# Pressure_sensor.net
KiCad netlist of a schematic drawn in Altium Designer
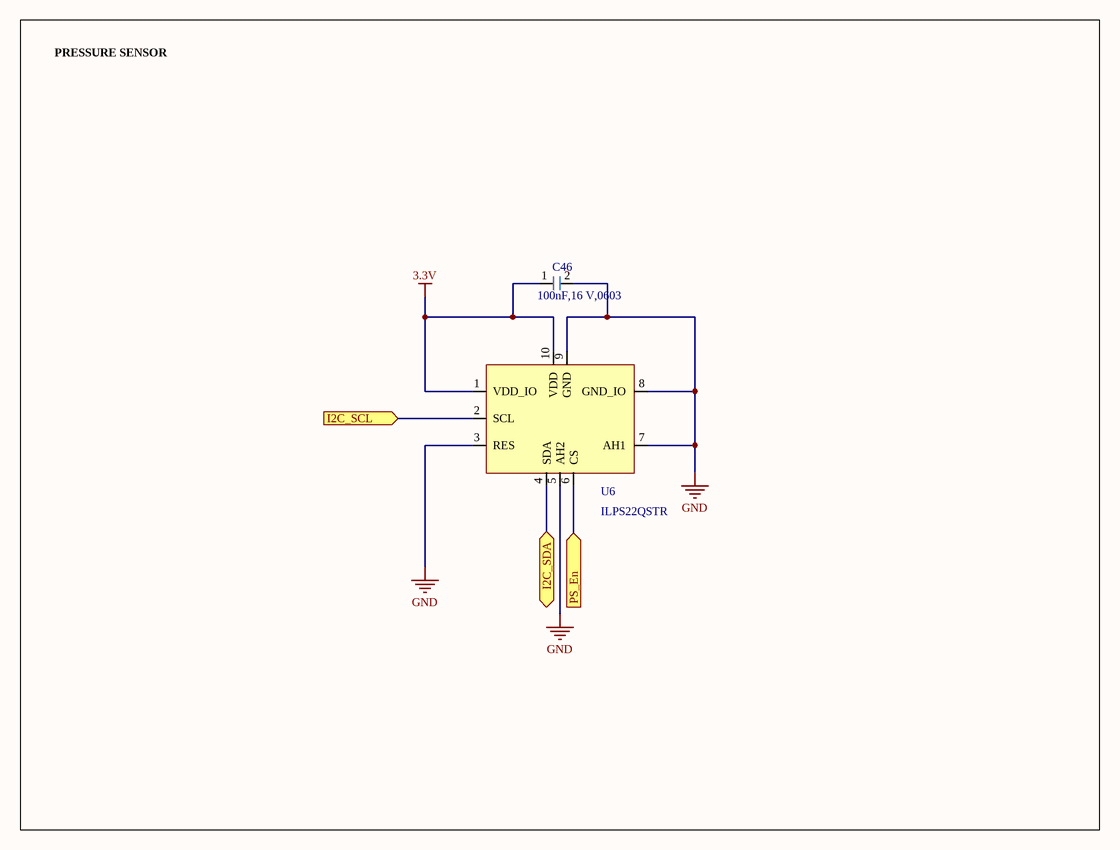
[diagram p0: Pressure sensor.SchDoc]

(export (version "E")
  (design (tool "Eeschema 10.0.6"))
  (components
    (comp (ref "C46")
      (value "CC0603KRX7R7BB104")
      (footprint "BMS_V2.1_Adv:CAPC1608X05N 0603")
      (description "Multilayer Ceramic Capacitor, 100 nF, 16V, ±10%,  X7R 0603 [1608 Metric]")
      (fields
        (field (name "MANUFACTURER") "Yageo")
        (field (name "TOLERANCE") "10%")
        (field (name "VALUE DISPLAY") "100nF,16 V,0603")
      )
      (libsource (lib "BMS_V2.1_Adv") (part "Cap_CC0603KRX7R7BB104"))
    )
    (comp (ref "U6")
      (value "ILPS22QSTR")
      (footprint "BMS_V2.1_Adv:QFN50P200X200X80-10N")
      (description "Pressure Sensor 3.77PSI ~ 58.89PSI (26kPa ~ 406kPa) Absolute 24 b 10-WFLGA")
      (fields (field (name "MANUFACTURER") "ST") (field (name "VOLTAGE") "3.3V"))
      (libsource (lib "BMS_V2.1_Adv") (part "IC_ILPS22QSTR"))
    )
  )
  (nets
    (net (code "1") (name "/I2C_SCL") (class "Default")
      (node (ref "U6") (pin "2") (pinfunction "SCL_2") (pintype "passive"))
    )
    (net (code "2") (name "/I2C_SDA") (class "Default")
      (node (ref "U6") (pin "4") (pinfunction "SDA_4") (pintype "passive"))
    )
    (net (code "3") (name "/PS_En") (class "Default")
      (node (ref "U6") (pin "6") (pinfunction "CS_6") (pintype "passive"))
    )
    (net (code "4") (name "3.3V") (class "Default")
      (node (ref "C46") (pin "1") (pinfunction "1_1") (pintype "passive"))
      (node (ref "U6") (pin "1") (pinfunction "VDD_IO_1") (pintype "passive"))
      (node (ref "U6") (pin "10") (pinfunction "VDD_10") (pintype "passive"))
    )
    (net (code "5") (name "GND") (class "Default")
      (node (ref "C46") (pin "2") (pinfunction "2_2") (pintype "passive"))
      (node (ref "U6") (pin "3") (pinfunction "RES_3") (pintype "passive"))
      (node (ref "U6") (pin "5") (pinfunction "AH2_5") (pintype "passive"))
      (node (ref "U6") (pin "7") (pinfunction "AH1_7") (pintype "passive"))
      (node (ref "U6") (pin "8") (pinfunction "GND_IO_8") (pintype "passive"))
      (node (ref "U6") (pin "9") (pinfunction "GND_9") (pintype "passive"))
    )
  )
)
